# UniversalFullBridge.net
KiCad netlist of a schematic drawn in Altium Designer
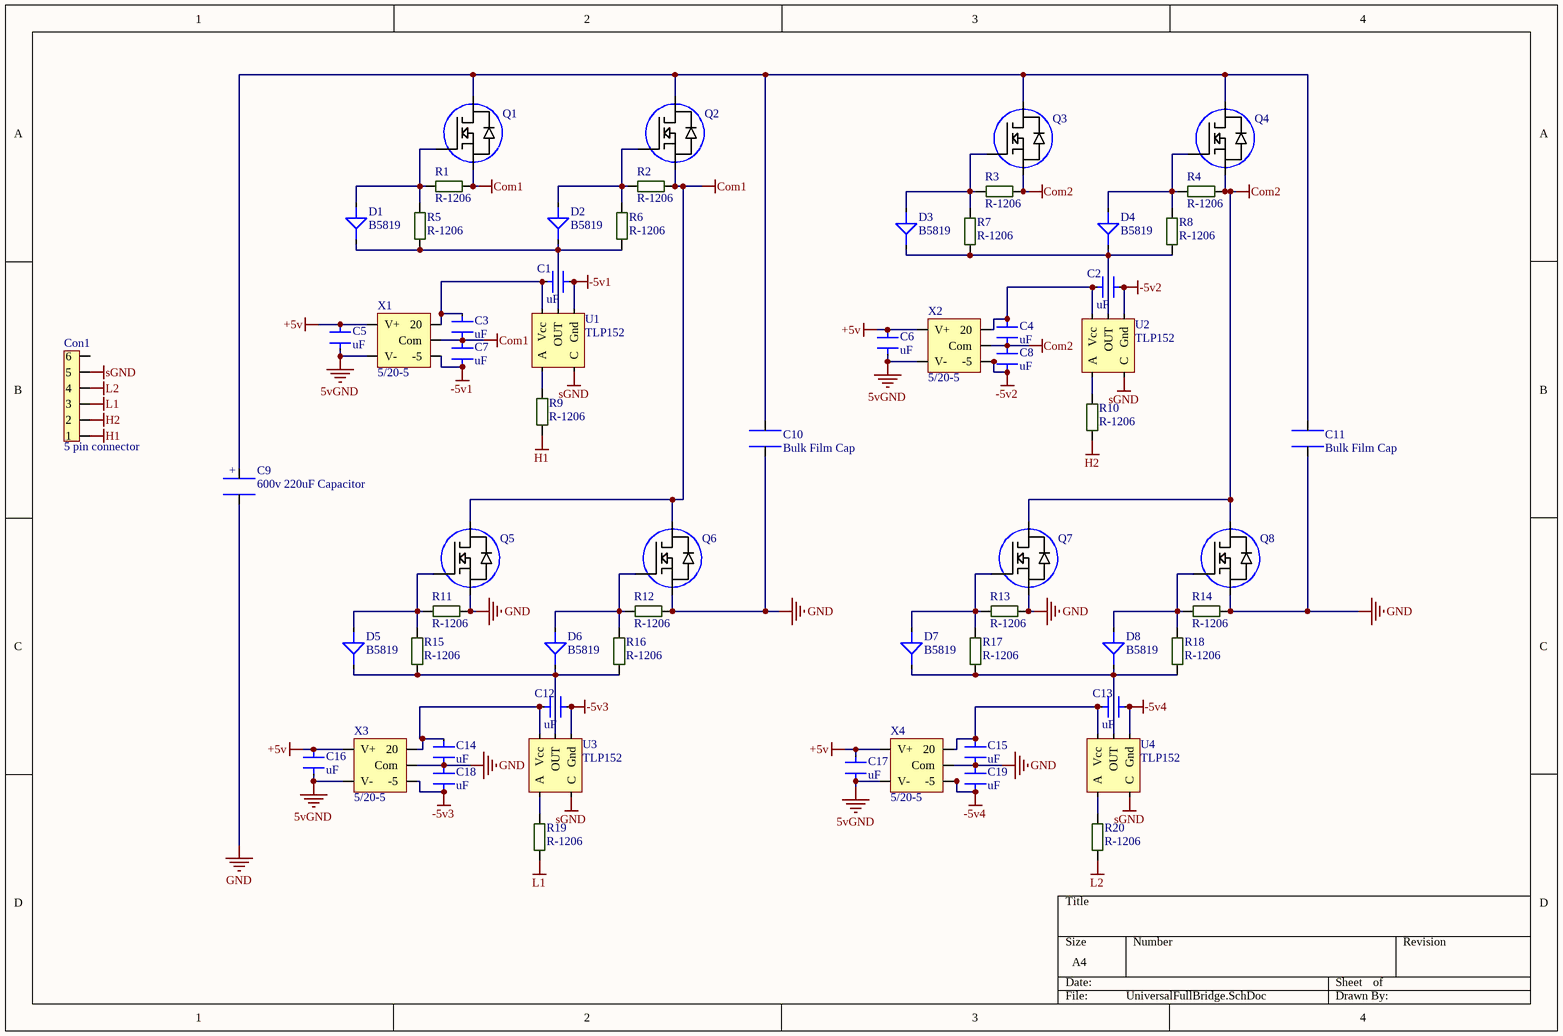
[diagram p0: UniversalFullBridge.SchDoc]

(export (version "E")
  (design (tool "Eeschema 10.0.6"))
  (components
    (comp (ref "C1")
      (value "uF")
      (footprint "C-1206W")
      (libsource (lib "UniversalFullBridge") (part "C-1206"))
    )
    (comp (ref "C2")
      (value "uF")
      (footprint "C-1206W")
      (libsource (lib "UniversalFullBridge") (part "C-1206"))
    )
    (comp (ref "C3")
      (value "uF")
      (footprint "C-1206W")
      (libsource (lib "UniversalFullBridge") (part "C-1206"))
    )
    (comp (ref "C4")
      (value "uF")
      (footprint "C-1206W")
      (libsource (lib "UniversalFullBridge") (part "C-1206"))
    )
    (comp (ref "C5")
      (value "uF")
      (footprint "C-1206W")
      (libsource (lib "UniversalFullBridge") (part "C-1206"))
    )
    (comp (ref "C6")
      (value "uF")
      (footprint "C-1206W")
      (libsource (lib "UniversalFullBridge") (part "C-1206"))
    )
    (comp (ref "C7")
      (value "uF")
      (footprint "C-1206W")
      (libsource (lib "UniversalFullBridge") (part "C-1206"))
    )
    (comp (ref "C8")
      (value "uF")
      (footprint "C-1206W")
      (libsource (lib "UniversalFullBridge") (part "C-1206"))
    )
    (comp (ref "C9")
      (value "600v 220uF Capacitor")
      (footprint "600v Capacitor")
      (libsource (lib "UniversalFullBridge") (part "600v 220uF Capacitor"))
    )
    (comp (ref "C10")
      (value "Bulk Film Cap")
      (footprint "Bulk cappacitor")
      (libsource (lib "UniversalFullBridge") (part "3300pF Bulk Capacitor"))
    )
    (comp (ref "C11")
      (value "Bulk Film Cap")
      (footprint "Bulk cappacitor")
      (libsource (lib "UniversalFullBridge") (part "3300pF Bulk Capacitor"))
    )
    (comp (ref "C12")
      (value "uF")
      (footprint "C-1206W")
      (libsource (lib "UniversalFullBridge") (part "C-1206"))
    )
    (comp (ref "C13")
      (value "uF")
      (footprint "C-1206W")
      (libsource (lib "UniversalFullBridge") (part "C-1206"))
    )
    (comp (ref "C14")
      (value "uF")
      (footprint "C-1206W")
      (libsource (lib "UniversalFullBridge") (part "C-1206"))
    )
    (comp (ref "C15")
      (value "uF")
      (footprint "C-1206W")
      (libsource (lib "UniversalFullBridge") (part "C-1206"))
    )
    (comp (ref "C16")
      (value "uF")
      (footprint "C-1206W")
      (libsource (lib "UniversalFullBridge") (part "C-1206"))
    )
    (comp (ref "C17")
      (value "uF")
      (footprint "C-1206W")
      (libsource (lib "UniversalFullBridge") (part "C-1206"))
    )
    (comp (ref "C18")
      (value "uF")
      (footprint "C-1206W")
      (libsource (lib "UniversalFullBridge") (part "C-1206"))
    )
    (comp (ref "C19")
      (value "uF")
      (footprint "C-1206W")
      (libsource (lib "UniversalFullBridge") (part "C-1206"))
    )
    (comp (ref "Con1")
      (value "5 pin connector")
      (footprint "pinheader")
      (libsource (lib "UniversalFullBridge") (part "5 pin connector"))
    )
    (comp (ref "D1")
      (value "B5819")
      (footprint "B5819")
      (libsource (lib "UniversalFullBridge") (part "B5819"))
    )
    (comp (ref "D2")
      (value "B5819")
      (footprint "B5819")
      (libsource (lib "UniversalFullBridge") (part "B5819"))
    )
    (comp (ref "D3")
      (value "B5819")
      (footprint "B5819")
      (libsource (lib "UniversalFullBridge") (part "B5819"))
    )
    (comp (ref "D4")
      (value "B5819")
      (footprint "B5819")
      (libsource (lib "UniversalFullBridge") (part "B5819"))
    )
    (comp (ref "D5")
      (value "B5819")
      (footprint "B5819")
      (libsource (lib "UniversalFullBridge") (part "B5819"))
    )
    (comp (ref "D6")
      (value "B5819")
      (footprint "B5819")
      (libsource (lib "UniversalFullBridge") (part "B5819"))
    )
    (comp (ref "D7")
      (value "B5819")
      (footprint "B5819")
      (libsource (lib "UniversalFullBridge") (part "B5819"))
    )
    (comp (ref "D8")
      (value "B5819")
      (footprint "B5819")
      (libsource (lib "UniversalFullBridge") (part "B5819"))
    )
    (comp (ref "Q1")
      (value "To263Mosfet")
      (footprint "To263Mosfet")
      (libsource (lib "UniversalFullBridge") (part "To263Mosfet"))
    )
    (comp (ref "Q2")
      (value "To263Mosfet")
      (footprint "To263Mosfet")
      (libsource (lib "UniversalFullBridge") (part "To263Mosfet"))
    )
    (comp (ref "Q3")
      (value "To263Mosfet")
      (footprint "To263Mosfet")
      (libsource (lib "UniversalFullBridge") (part "To263Mosfet"))
    )
    (comp (ref "Q4")
      (value "To263Mosfet")
      (footprint "To263Mosfet")
      (libsource (lib "UniversalFullBridge") (part "To263Mosfet"))
    )
    (comp (ref "Q5")
      (value "To263Mosfet")
      (footprint "To263Mosfet")
      (libsource (lib "UniversalFullBridge") (part "To263Mosfet"))
    )
    (comp (ref "Q6")
      (value "To263Mosfet")
      (footprint "To263Mosfet")
      (libsource (lib "UniversalFullBridge") (part "To263Mosfet"))
    )
    (comp (ref "Q7")
      (value "To263Mosfet")
      (footprint "To263Mosfet")
      (libsource (lib "UniversalFullBridge") (part "To263Mosfet"))
    )
    (comp (ref "Q8")
      (value "To263Mosfet")
      (footprint "To263Mosfet")
      (libsource (lib "UniversalFullBridge") (part "To263Mosfet"))
    )
    (comp (ref "R1")
      (value "R-1206")
      (footprint "R-1206W")
      (description "Res1206")
      (libsource (lib "UniversalFullBridge") (part "R-1206"))
    )
    (comp (ref "R2")
      (value "R-1206")
      (footprint "R-1206W")
      (description "Res1206")
      (libsource (lib "UniversalFullBridge") (part "R-1206"))
    )
    (comp (ref "R3")
      (value "R-1206")
      (footprint "R-1206W")
      (description "Res1206")
      (libsource (lib "UniversalFullBridge") (part "R-1206"))
    )
    (comp (ref "R4")
      (value "R-1206")
      (footprint "R-1206W")
      (description "Res1206")
      (libsource (lib "UniversalFullBridge") (part "R-1206"))
    )
    (comp (ref "R5")
      (value "R-1206")
      (footprint "R-1206W")
      (description "Res1206")
      (libsource (lib "UniversalFullBridge") (part "R-1206"))
    )
    (comp (ref "R6")
      (value "R-1206")
      (footprint "R-1206W")
      (description "Res1206")
      (libsource (lib "UniversalFullBridge") (part "R-1206"))
    )
    (comp (ref "R7")
      (value "R-1206")
      (footprint "R-1206W")
      (description "Res1206")
      (libsource (lib "UniversalFullBridge") (part "R-1206"))
    )
    (comp (ref "R8")
      (value "R-1206")
      (footprint "R-1206W")
      (description "Res1206")
      (libsource (lib "UniversalFullBridge") (part "R-1206"))
    )
    (comp (ref "R9")
      (value "R-1206")
      (footprint "R-1206W")
      (description "Res1206")
      (libsource (lib "UniversalFullBridge") (part "R-1206"))
    )
    (comp (ref "R10")
      (value "R-1206")
      (footprint "R-1206W")
      (description "Res1206")
      (libsource (lib "UniversalFullBridge") (part "R-1206"))
    )
    (comp (ref "R11")
      (value "R-1206")
      (footprint "R-1206W")
      (description "Res1206")
      (libsource (lib "UniversalFullBridge") (part "R-1206"))
    )
    (comp (ref "R12")
      (value "R-1206")
      (footprint "R-1206W")
      (description "Res1206")
      (libsource (lib "UniversalFullBridge") (part "R-1206"))
    )
    (comp (ref "R13")
      (value "R-1206")
      (footprint "R-1206W")
      (description "Res1206")
      (libsource (lib "UniversalFullBridge") (part "R-1206"))
    )
    (comp (ref "R14")
      (value "R-1206")
      (footprint "R-1206W")
      (description "Res1206")
      (libsource (lib "UniversalFullBridge") (part "R-1206"))
    )
    (comp (ref "R15")
      (value "R-1206")
      (footprint "R-1206W")
      (description "Res1206")
      (libsource (lib "UniversalFullBridge") (part "R-1206"))
    )
    (comp (ref "R16")
      (value "R-1206")
      (footprint "R-1206W")
      (description "Res1206")
      (libsource (lib "UniversalFullBridge") (part "R-1206"))
    )
    (comp (ref "R17")
      (value "R-1206")
      (footprint "R-1206W")
      (description "Res1206")
      (libsource (lib "UniversalFullBridge") (part "R-1206"))
    )
    (comp (ref "R18")
      (value "R-1206")
      (footprint "R-1206W")
      (description "Res1206")
      (libsource (lib "UniversalFullBridge") (part "R-1206"))
    )
    (comp (ref "R19")
      (value "R-1206")
      (footprint "R-1206W")
      (description "Res1206")
      (libsource (lib "UniversalFullBridge") (part "R-1206"))
    )
    (comp (ref "R20")
      (value "R-1206")
      (footprint "R-1206W")
      (description "Res1206")
      (libsource (lib "UniversalFullBridge") (part "R-1206"))
    )
    (comp (ref "U1")
      (value "TLP152")
      (footprint "tlp152")
      (libsource (lib "UniversalFullBridge") (part "TLP152"))
    )
    (comp (ref "U2")
      (value "TLP152")
      (footprint "tlp152")
      (libsource (lib "UniversalFullBridge") (part "TLP152"))
    )
    (comp (ref "U3")
      (value "TLP152")
      (footprint "tlp152")
      (libsource (lib "UniversalFullBridge") (part "TLP152"))
    )
    (comp (ref "U4")
      (value "TLP152")
      (footprint "tlp152")
      (libsource (lib "UniversalFullBridge") (part "TLP152"))
    )
    (comp (ref "X1")
      (value "5/20-5")
      (footprint "sip7DCDC converter")
      (libsource (lib "UniversalFullBridge") (part "DC/DC Coınverter"))
    )
    (comp (ref "X2")
      (value "5/20-5")
      (footprint "sip7DCDC converter")
      (libsource (lib "UniversalFullBridge") (part "DC/DC Coınverter"))
    )
    (comp (ref "X3")
      (value "5/20-5")
      (footprint "sip7DCDC converter")
      (libsource (lib "UniversalFullBridge") (part "DC/DC Coınverter"))
    )
    (comp (ref "X4")
      (value "5/20-5")
      (footprint "sip7DCDC converter")
      (libsource (lib "UniversalFullBridge") (part "DC/DC Coınverter"))
    )
  )
  (nets
    (net (code "1") (name "+5v") (class "Default")
      (node (ref "C16") (pin "2") (pinfunction "2_2") (pintype "passive"))
      (node (ref "C17") (pin "2") (pinfunction "2_2") (pintype "passive"))
      (node (ref "C5") (pin "2") (pinfunction "2_2") (pintype "passive"))
      (node (ref "C6") (pin "2") (pinfunction "2_2") (pintype "passive"))
      (node (ref "X1") (pin "1") (pinfunction "V+_1") (pintype "passive"))
      (node (ref "X2") (pin "1") (pinfunction "V+_1") (pintype "passive"))
      (node (ref "X3") (pin "1") (pinfunction "V+_1") (pintype "passive"))
      (node (ref "X4") (pin "1") (pinfunction "V+_1") (pintype "passive"))
    )
    (net (code "2") (name "-5v1") (class "Default")
      (node (ref "C1") (pin "2") (pinfunction "2_2") (pintype "passive"))
      (node (ref "C7") (pin "1") (pinfunction "1_1") (pintype "passive"))
      (node (ref "U1") (pin "4") (pinfunction "Gnd_4") (pintype "passive"))
      (node (ref "X1") (pin "5") (pinfunction "-5_5") (pintype "passive"))
    )
    (net (code "3") (name "-5v2") (class "Default")
      (node (ref "C2") (pin "2") (pinfunction "2_2") (pintype "passive"))
      (node (ref "C8") (pin "1") (pinfunction "1_1") (pintype "passive"))
      (node (ref "U2") (pin "4") (pinfunction "Gnd_4") (pintype "passive"))
      (node (ref "X2") (pin "5") (pinfunction "-5_5") (pintype "passive"))
    )
    (net (code "4") (name "-5v3") (class "Default")
      (node (ref "C12") (pin "2") (pinfunction "2_2") (pintype "passive"))
      (node (ref "C18") (pin "1") (pinfunction "1_1") (pintype "passive"))
      (node (ref "U3") (pin "4") (pinfunction "Gnd_4") (pintype "passive"))
      (node (ref "X3") (pin "5") (pinfunction "-5_5") (pintype "passive"))
    )
    (net (code "5") (name "-5v4") (class "Default")
      (node (ref "C13") (pin "2") (pinfunction "2_2") (pintype "passive"))
      (node (ref "C19") (pin "1") (pinfunction "1_1") (pintype "passive"))
      (node (ref "U4") (pin "4") (pinfunction "Gnd_4") (pintype "passive"))
      (node (ref "X4") (pin "5") (pinfunction "-5_5") (pintype "passive"))
    )
    (net (code "6") (name "5vGND") (class "Default")
      (node (ref "C16") (pin "1") (pinfunction "1_1") (pintype "passive"))
      (node (ref "C17") (pin "1") (pinfunction "1_1") (pintype "passive"))
      (node (ref "C5") (pin "1") (pinfunction "1_1") (pintype "passive"))
      (node (ref "C6") (pin "1") (pinfunction "1_1") (pintype "passive"))
      (node (ref "X1") (pin "2") (pinfunction "V-_2") (pintype "passive"))
      (node (ref "X2") (pin "2") (pinfunction "V-_2") (pintype "passive"))
      (node (ref "X3") (pin "2") (pinfunction "V-_2") (pintype "passive"))
      (node (ref "X4") (pin "2") (pinfunction "V-_2") (pintype "passive"))
    )
    (net (code "7") (name "Com1") (class "Default")
      (node (ref "C3") (pin "1") (pinfunction "1_1") (pintype "passive"))
      (node (ref "C7") (pin "2") (pinfunction "2_2") (pintype "passive"))
      (node (ref "Q1") (pin "3") (pinfunction "S_3") (pintype "passive"))
      (node (ref "Q2") (pin "3") (pinfunction "S_3") (pintype "passive"))
      (node (ref "Q5") (pin "2") (pinfunction "D_2") (pintype "passive"))
      (node (ref "Q6") (pin "2") (pinfunction "D_2") (pintype "passive"))
      (node (ref "R1") (pin "1") (pinfunction "1_1") (pintype "passive"))
      (node (ref "R2") (pin "1") (pinfunction "1_1") (pintype "passive"))
      (node (ref "X1") (pin "6") (pinfunction "Com_6") (pintype "passive"))
    )
    (net (code "8") (name "Com2") (class "Default")
      (node (ref "C4") (pin "1") (pinfunction "1_1") (pintype "passive"))
      (node (ref "C8") (pin "2") (pinfunction "2_2") (pintype "passive"))
      (node (ref "Q3") (pin "3") (pinfunction "S_3") (pintype "passive"))
      (node (ref "Q4") (pin "3") (pinfunction "S_3") (pintype "passive"))
      (node (ref "Q7") (pin "2") (pinfunction "D_2") (pintype "passive"))
      (node (ref "Q8") (pin "2") (pinfunction "D_2") (pintype "passive"))
      (node (ref "R3") (pin "1") (pinfunction "1_1") (pintype "passive"))
      (node (ref "R4") (pin "1") (pinfunction "1_1") (pintype "passive"))
      (node (ref "X2") (pin "6") (pinfunction "Com_6") (pintype "passive"))
    )
    (net (code "9") (name "GND") (class "Default")
      (node (ref "C10") (pin "2") (pinfunction "2_2") (pintype "passive"))
      (node (ref "C11") (pin "2") (pinfunction "2_2") (pintype "passive"))
      (node (ref "C14") (pin "1") (pinfunction "1_1") (pintype "passive"))
      (node (ref "C15") (pin "1") (pinfunction "1_1") (pintype "passive"))
      (node (ref "C18") (pin "2") (pinfunction "2_2") (pintype "passive"))
      (node (ref "C19") (pin "2") (pinfunction "2_2") (pintype "passive"))
      (node (ref "C9") (pin "2") (pinfunction "2_2") (pintype "passive"))
      (node (ref "Q5") (pin "3") (pinfunction "S_3") (pintype "passive"))
      (node (ref "Q6") (pin "3") (pinfunction "S_3") (pintype "passive"))
      (node (ref "Q7") (pin "3") (pinfunction "S_3") (pintype "passive"))
      (node (ref "Q8") (pin "3") (pinfunction "S_3") (pintype "passive"))
      (node (ref "R11") (pin "1") (pinfunction "1_1") (pintype "passive"))
      (node (ref "R12") (pin "1") (pinfunction "1_1") (pintype "passive"))
      (node (ref "R13") (pin "1") (pinfunction "1_1") (pintype "passive"))
      (node (ref "R14") (pin "1") (pinfunction "1_1") (pintype "passive"))
      (node (ref "X3") (pin "6") (pinfunction "Com_6") (pintype "passive"))
      (node (ref "X4") (pin "6") (pinfunction "Com_6") (pintype "passive"))
    )
    (net (code "10") (name "H1") (class "Default")
      (node (ref "Con1") (pin "1") (pinfunction "1_1") (pintype "passive"))
      (node (ref "R9") (pin "1") (pinfunction "1_1") (pintype "passive"))
    )
    (net (code "11") (name "H2") (class "Default")
      (node (ref "Con1") (pin "2") (pinfunction "2_2") (pintype "passive"))
      (node (ref "R10") (pin "1") (pinfunction "1_1") (pintype "passive"))
    )
    (net (code "12") (name "L1") (class "Default")
      (node (ref "Con1") (pin "3") (pinfunction "3_3") (pintype "passive"))
      (node (ref "R19") (pin "1") (pinfunction "1_1") (pintype "passive"))
    )
    (net (code "13") (name "L2") (class "Default")
      (node (ref "Con1") (pin "4") (pinfunction "4_4") (pintype "passive"))
      (node (ref "R20") (pin "1") (pinfunction "1_1") (pintype "passive"))
    )
    (net (code "14") (name "Net-(Q1-D)") (class "Default")
      (node (ref "C10") (pin "1") (pinfunction "1_1") (pintype "passive"))
      (node (ref "C11") (pin "1") (pinfunction "1_1") (pintype "passive"))
      (node (ref "C9") (pin "1") (pinfunction "1_1") (pintype "passive"))
      (node (ref "Q1") (pin "2") (pinfunction "D_2") (pintype "passive"))
      (node (ref "Q2") (pin "2") (pinfunction "D_2") (pintype "passive"))
      (node (ref "Q3") (pin "2") (pinfunction "D_2") (pintype "passive"))
      (node (ref "Q4") (pin "2") (pinfunction "D_2") (pintype "passive"))
    )
    (net (code "15") (name "Net-(Q1-G)") (class "Default")
      (node (ref "D1") (pin "2") (pinfunction "2_2") (pintype "passive"))
      (node (ref "Q1") (pin "1") (pinfunction "G_1") (pintype "passive"))
      (node (ref "R1") (pin "2") (pinfunction "2_2") (pintype "passive"))
      (node (ref "R5") (pin "2") (pinfunction "2_2") (pintype "passive"))
    )
    (net (code "16") (name "Net-(Q2-G)") (class "Default")
      (node (ref "D2") (pin "2") (pinfunction "2_2") (pintype "passive"))
      (node (ref "Q2") (pin "1") (pinfunction "G_1") (pintype "passive"))
      (node (ref "R2") (pin "2") (pinfunction "2_2") (pintype "passive"))
      (node (ref "R6") (pin "2") (pinfunction "2_2") (pintype "passive"))
    )
    (net (code "17") (name "Net-(Q3-G)") (class "Default")
      (node (ref "D3") (pin "2") (pinfunction "2_2") (pintype "passive"))
      (node (ref "Q3") (pin "1") (pinfunction "G_1") (pintype "passive"))
      (node (ref "R3") (pin "2") (pinfunction "2_2") (pintype "passive"))
      (node (ref "R7") (pin "2") (pinfunction "2_2") (pintype "passive"))
    )
    (net (code "18") (name "Net-(Q4-G)") (class "Default")
      (node (ref "D4") (pin "2") (pinfunction "2_2") (pintype "passive"))
      (node (ref "Q4") (pin "1") (pinfunction "G_1") (pintype "passive"))
      (node (ref "R4") (pin "2") (pinfunction "2_2") (pintype "passive"))
      (node (ref "R8") (pin "2") (pinfunction "2_2") (pintype "passive"))
    )
    (net (code "19") (name "Net-(Q5-G)") (class "Default")
      (node (ref "D5") (pin "2") (pinfunction "2_2") (pintype "passive"))
      (node (ref "Q5") (pin "1") (pinfunction "G_1") (pintype "passive"))
      (node (ref "R11") (pin "2") (pinfunction "2_2") (pintype "passive"))
      (node (ref "R15") (pin "2") (pinfunction "2_2") (pintype "passive"))
    )
    (net (code "20") (name "Net-(Q6-G)") (class "Default")
      (node (ref "D6") (pin "2") (pinfunction "2_2") (pintype "passive"))
      (node (ref "Q6") (pin "1") (pinfunction "G_1") (pintype "passive"))
      (node (ref "R12") (pin "2") (pinfunction "2_2") (pintype "passive"))
      (node (ref "R16") (pin "2") (pinfunction "2_2") (pintype "passive"))
    )
    (net (code "21") (name "Net-(Q7-G)") (class "Default")
      (node (ref "D7") (pin "2") (pinfunction "2_2") (pintype "passive"))
      (node (ref "Q7") (pin "1") (pinfunction "G_1") (pintype "passive"))
      (node (ref "R13") (pin "2") (pinfunction "2_2") (pintype "passive"))
      (node (ref "R17") (pin "2") (pinfunction "2_2") (pintype "passive"))
    )
    (net (code "22") (name "Net-(Q8-G)") (class "Default")
      (node (ref "D8") (pin "2") (pinfunction "2_2") (pintype "passive"))
      (node (ref "Q8") (pin "1") (pinfunction "G_1") (pintype "passive"))
      (node (ref "R14") (pin "2") (pinfunction "2_2") (pintype "passive"))
      (node (ref "R18") (pin "2") (pinfunction "2_2") (pintype "passive"))
    )
    (net (code "23") (name "Net-(U1-A)") (class "Default")
      (node (ref "R9") (pin "2") (pinfunction "2_2") (pintype "passive"))
      (node (ref "U1") (pin "1") (pinfunction "A_1") (pintype "passive"))
    )
    (net (code "24") (name "Net-(U1-OUT)") (class "Default")
      (node (ref "D1") (pin "1") (pinfunction "1_1") (pintype "passive"))
      (node (ref "D2") (pin "1") (pinfunction "1_1") (pintype "passive"))
      (node (ref "R5") (pin "1") (pinfunction "1_1") (pintype "passive"))
      (node (ref "R6") (pin "1") (pinfunction "1_1") (pintype "passive"))
      (node (ref "U1") (pin "5") (pinfunction "OUT_5") (pintype "passive"))
    )
    (net (code "25") (name "Net-(U1-Vcc)") (class "Default")
      (node (ref "C1") (pin "1") (pinfunction "1_1") (pintype "passive"))
      (node (ref "C3") (pin "2") (pinfunction "2_2") (pintype "passive"))
      (node (ref "U1") (pin "6") (pinfunction "Vcc_6") (pintype "passive"))
      (node (ref "X1") (pin "7") (pinfunction "20_7") (pintype "passive"))
    )
    (net (code "26") (name "Net-(U2-A)") (class "Default")
      (node (ref "R10") (pin "2") (pinfunction "2_2") (pintype "passive"))
      (node (ref "U2") (pin "1") (pinfunction "A_1") (pintype "passive"))
    )
    (net (code "27") (name "Net-(U2-OUT)") (class "Default")
      (node (ref "D3") (pin "1") (pinfunction "1_1") (pintype "passive"))
      (node (ref "D4") (pin "1") (pinfunction "1_1") (pintype "passive"))
      (node (ref "R7") (pin "1") (pinfunction "1_1") (pintype "passive"))
      (node (ref "R8") (pin "1") (pinfunction "1_1") (pintype "passive"))
      (node (ref "U2") (pin "5") (pinfunction "OUT_5") (pintype "passive"))
    )
    (net (code "28") (name "Net-(U2-Vcc)") (class "Default")
      (node (ref "C2") (pin "1") (pinfunction "1_1") (pintype "passive"))
      (node (ref "C4") (pin "2") (pinfunction "2_2") (pintype "passive"))
      (node (ref "U2") (pin "6") (pinfunction "Vcc_6") (pintype "passive"))
      (node (ref "X2") (pin "7") (pinfunction "20_7") (pintype "passive"))
    )
    (net (code "29") (name "Net-(U3-A)") (class "Default")
      (node (ref "R19") (pin "2") (pinfunction "2_2") (pintype "passive"))
      (node (ref "U3") (pin "1") (pinfunction "A_1") (pintype "passive"))
    )
    (net (code "30") (name "Net-(U3-OUT)") (class "Default")
      (node (ref "D5") (pin "1") (pinfunction "1_1") (pintype "passive"))
      (node (ref "D6") (pin "1") (pinfunction "1_1") (pintype "passive"))
      (node (ref "R15") (pin "1") (pinfunction "1_1") (pintype "passive"))
      (node (ref "R16") (pin "1") (pinfunction "1_1") (pintype "passive"))
      (node (ref "U3") (pin "5") (pinfunction "OUT_5") (pintype "passive"))
    )
    (net (code "31") (name "Net-(U3-Vcc)") (class "Default")
      (node (ref "C12") (pin "1") (pinfunction "1_1") (pintype "passive"))
      (node (ref "C14") (pin "2") (pinfunction "2_2") (pintype "passive"))
      (node (ref "U3") (pin "6") (pinfunction "Vcc_6") (pintype "passive"))
      (node (ref "X3") (pin "7") (pinfunction "20_7") (pintype "passive"))
    )
    (net (code "32") (name "Net-(U4-A)") (class "Default")
      (node (ref "R20") (pin "2") (pinfunction "2_2") (pintype "passive"))
      (node (ref "U4") (pin "1") (pinfunction "A_1") (pintype "passive"))
    )
    (net (code "33") (name "Net-(U4-OUT)") (class "Default")
      (node (ref "D7") (pin "1") (pinfunction "1_1") (pintype "passive"))
      (node (ref "D8") (pin "1") (pinfunction "1_1") (pintype "passive"))
      (node (ref "R17") (pin "1") (pinfunction "1_1") (pintype "passive"))
      (node (ref "R18") (pin "1") (pinfunction "1_1") (pintype "passive"))
      (node (ref "U4") (pin "5") (pinfunction "OUT_5") (pintype "passive"))
    )
    (net (code "34") (name "Net-(U4-Vcc)") (class "Default")
      (node (ref "C13") (pin "1") (pinfunction "1_1") (pintype "passive"))
      (node (ref "C15") (pin "2") (pinfunction "2_2") (pintype "passive"))
      (node (ref "U4") (pin "6") (pinfunction "Vcc_6") (pintype "passive"))
      (node (ref "X4") (pin "7") (pinfunction "20_7") (pintype "passive"))
    )
    (net (code "35") (name "sGND") (class "Default")
      (node (ref "Con1") (pin "5") (pinfunction "5_5") (pintype "passive"))
      (node (ref "U1") (pin "3") (pinfunction "C_3") (pintype "passive"))
      (node (ref "U2") (pin "3") (pinfunction "C_3") (pintype "passive"))
      (node (ref "U3") (pin "3") (pinfunction "C_3") (pintype "passive"))
      (node (ref "U4") (pin "3") (pinfunction "C_3") (pintype "passive"))
    )
    (net (code "36") (name "unconnected-(Con1-Pad6)") (class "Default")
      (node (ref "Con1") (pin "6") (pinfunction "6_6") (pintype "passive"))
    )
  )
)
